# Knot_Thing_MCU.net
KiCad netlist of a schematic drawn in Altium Designer
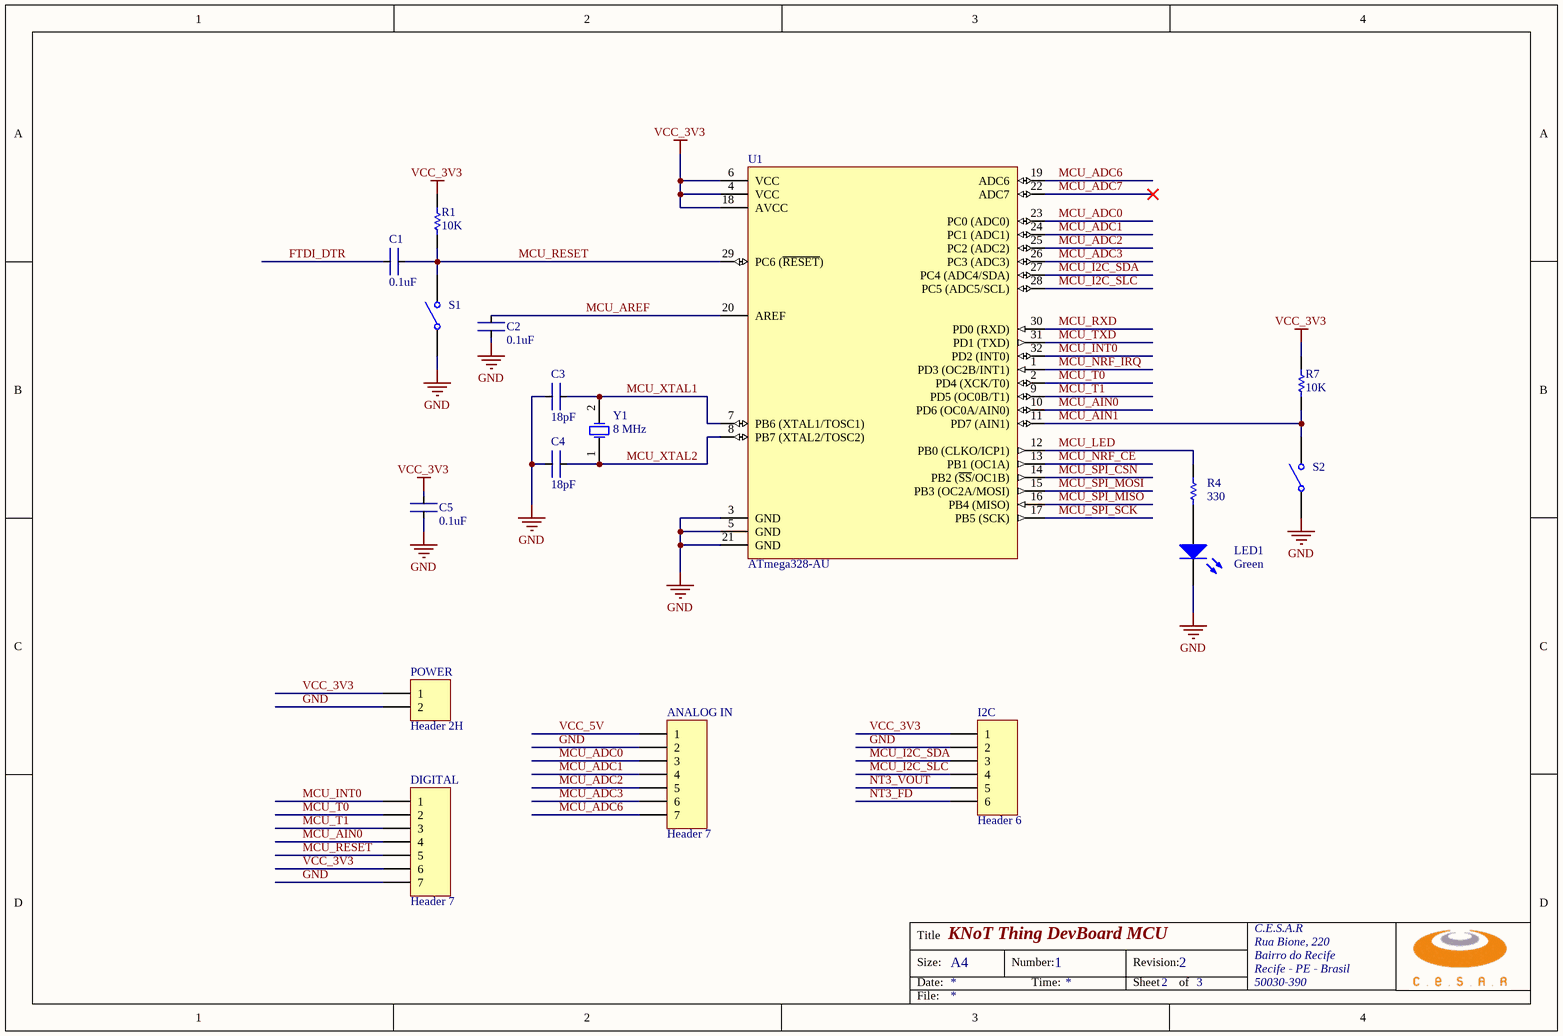
[diagram p0: Knot_Thing_MCU.SchDoc]

(export (version "E")
  (design (tool "Eeschema 10.0.6"))
  (components
    (comp (ref "ANALOG IN")
      (value "Header 7")
      (footprint "HDR1X7")
      (description "Header, 7-Pin")
      (fields (field (name "PUBLISHER") "Altium Limited"))
      (libsource (lib "KNoT_Thing") (part "Header 7"))
    )
    (comp (ref "C1")
      (value "0.1uF")
      (footprint "CAPC1005L")
      (description "Chip Capacitor 0402 (1005 metric)")
      (fields (field (name "Comment") "Cap_0402"))
      (libsource (lib "KNoT_Thing") (part "Capacitor_0402"))
    )
    (comp (ref "C2")
      (value "0.1uF")
      (footprint "CAPC1005L")
      (description "Chip Capacitor 0402 (1005 metric)")
      (fields (field (name "Comment") "Cap_0402"))
      (libsource (lib "KNoT_Thing") (part "Capacitor_0402"))
    )
    (comp (ref "C3")
      (value "18pF")
      (footprint "CAPC1005L")
      (description "Chip Capacitor 0402 (1005 metric)")
      (fields (field (name "Comment") "Cap_0402"))
      (libsource (lib "KNoT_Thing") (part "Capacitor_0402"))
    )
    (comp (ref "C4")
      (value "18pF")
      (footprint "CAPC1005L")
      (description "Chip Capacitor 0402 (1005 metric)")
      (fields (field (name "Comment") "Cap_0402"))
      (libsource (lib "KNoT_Thing") (part "Capacitor_0402"))
    )
    (comp (ref "C5")
      (value "0.1uF")
      (footprint "CAPC1005L")
      (description "Chip Capacitor 0402 (1005 metric)")
      (fields (field (name "Comment") "Cap_0402"))
      (libsource (lib "KNoT_Thing") (part "Capacitor_0402"))
    )
    (comp (ref "DIGITAL")
      (value "Header 7")
      (footprint "HDR1X7")
      (description "Header, 7-Pin")
      (fields (field (name "PUBLISHER") "Altium Limited"))
      (libsource (lib "KNoT_Thing") (part "Header 7"))
    )
    (comp (ref "I2C")
      (value "Header 6")
      (footprint "HDR1X6")
      (description "Header, 6-Pin")
      (fields (field (name "PUBLISHER") "Altium Limited"))
      (libsource (lib "KNoT_Thing") (part "Header 6"))
    )
    (comp (ref "LED1")
      (value "LED 0603")
      (footprint "0603_LED")
      (description "LED SMD 0603")
      (fields (field (name "COLOR") "Green"))
      (libsource (lib "KNoT_Thing") (part "LED 0603"))
    )
    (comp (ref "POWER")
      (value "Header 2H")
      (footprint "HDR1X2")
      (description "Header, 2-Pin, Right Angle")
      (fields (field (name "PUBLISHER") "Altium Limited"))
      (libsource (lib "KNoT_Thing") (part "Header 2H"))
    )
    (comp (ref "R1")
      (value "10K")
      (footprint "CAPC1005L")
      (fields (field (name "Comment") "RES_0402"))
      (libsource (lib "KNoT_Thing") (part "RES_0402"))
    )
    (comp (ref "R4")
      (value "330")
      (footprint "CAPC1005L")
      (fields (field (name "Comment") "RES_0402"))
      (libsource (lib "KNoT_Thing") (part "RES_0402"))
    )
    (comp (ref "R7")
      (value "10K")
      (footprint "CAPC1005L")
      (fields (field (name "Comment") "RES_0402"))
      (libsource (lib "KNoT_Thing") (part "RES_0402"))
    )
    (comp (ref "S1")
      (value "SW-SPST")
      (footprint "SWITCH TS-1181")
      (description "Single-Pole, Single-Throw Switch")
      (fields (field (name "PUBLISHER") "Altium Limited"))
      (libsource (lib "KNoT_Thing") (part "SW-SPST"))
    )
    (comp (ref "S2")
      (value "SW-SPST")
      (footprint "SWITCH TS-1181")
      (description "Single-Pole, Single-Throw Switch")
      (fields (field (name "PUBLISHER") "Altium Limited"))
      (libsource (lib "KNoT_Thing") (part "SW-SPST"))
    )
    (comp (ref "U1")
      (value "ATmega328-AU")
      (footprint "32A_L")
      (libsource (lib "KNoT_Thing") (part "ATmega328-AU"))
    )
    (comp (ref "Y1")
      (value "8 MHz")
      (footprint "CX5032GB")
      (description "Crystal FOXSLF/080-20")
      (libsource (lib "KNoT_Thing") (part "XTAL"))
    )
  )
  (nets
    (net (code "1") (name "/FTDI_DTR") (class "Default")
      (node (ref "C1") (pin "1") (pinfunction "1_1") (pintype "passive"))
    )
    (net (code "2") (name "/MCU_ADC0") (class "Default")
      (node (ref "ANALOG IN") (pin "3") (pinfunction "3_3") (pintype "passive"))
      (node (ref "U1") (pin "23") (pinfunction "PC0_(ADC0)_23") (pintype "bidirectional"))
    )
    (net (code "3") (name "/MCU_ADC1") (class "Default")
      (node (ref "ANALOG IN") (pin "4") (pinfunction "4_4") (pintype "passive"))
      (node (ref "U1") (pin "24") (pinfunction "PC1_(ADC1)_24") (pintype "bidirectional"))
    )
    (net (code "4") (name "/MCU_ADC2") (class "Default")
      (node (ref "ANALOG IN") (pin "5") (pinfunction "5_5") (pintype "passive"))
      (node (ref "U1") (pin "25") (pinfunction "PC2_(ADC2)_25") (pintype "bidirectional"))
    )
    (net (code "5") (name "/MCU_ADC3") (class "Default")
      (node (ref "ANALOG IN") (pin "6") (pinfunction "6_6") (pintype "passive"))
      (node (ref "U1") (pin "26") (pinfunction "PC3_(ADC3)_26") (pintype "bidirectional"))
    )
    (net (code "6") (name "/MCU_ADC6") (class "Default")
      (node (ref "ANALOG IN") (pin "7") (pinfunction "7_7") (pintype "passive"))
      (node (ref "U1") (pin "19") (pinfunction "ADC6_19") (pintype "bidirectional"))
    )
    (net (code "7") (name "/MCU_ADC7") (class "Default")
      (node (ref "U1") (pin "22") (pinfunction "ADC7_22") (pintype "bidirectional+no_connect"))
    )
    (net (code "8") (name "/MCU_AIN0") (class "Default")
      (node (ref "DIGITAL") (pin "4") (pinfunction "4_4") (pintype "passive"))
      (node (ref "U1") (pin "10") (pinfunction "PD6_(OC0A/AIN0)_10") (pintype "bidirectional"))
    )
    (net (code "9") (name "/MCU_AIN1") (class "Default")
      (node (ref "R7") (pin "1") (pinfunction "1_1") (pintype "passive"))
      (node (ref "S2") (pin "2") (pinfunction "NO_2") (pintype "passive"))
      (node (ref "U1") (pin "11") (pinfunction "PD7_(AIN1)_11") (pintype "bidirectional"))
    )
    (net (code "10") (name "/MCU_AREF") (class "Default")
      (node (ref "C2") (pin "2") (pinfunction "0_2") (pintype "passive"))
      (node (ref "U1") (pin "20") (pinfunction "AREF_20") (pintype "passive"))
    )
    (net (code "11") (name "/MCU_I2C_SDA") (class "Default")
      (node (ref "I2C") (pin "3") (pinfunction "3_3") (pintype "passive"))
      (node (ref "U1") (pin "27") (pinfunction "PC4_(ADC4/SDA)_27") (pintype "bidirectional"))
    )
    (net (code "12") (name "/MCU_I2C_SLC") (class "Default")
      (node (ref "I2C") (pin "4") (pinfunction "4_4") (pintype "passive"))
      (node (ref "U1") (pin "28") (pinfunction "PC5_(ADC5/SCL)_28") (pintype "bidirectional"))
    )
    (net (code "13") (name "/MCU_INT0") (class "Default")
      (node (ref "DIGITAL") (pin "1") (pinfunction "1_1") (pintype "passive"))
      (node (ref "U1") (pin "32") (pinfunction "PD2_(INT0)_32") (pintype "bidirectional"))
    )
    (net (code "14") (name "/MCU_LED") (class "Default")
      (node (ref "R4") (pin "2") (pinfunction "2_2") (pintype "passive"))
      (node (ref "U1") (pin "12") (pinfunction "PB0_(CLKO/ICP1)_12") (pintype "output"))
    )
    (net (code "15") (name "/MCU_NRF_CE") (class "Default")
      (node (ref "U1") (pin "13") (pinfunction "PB1_(OC1A)_13") (pintype "output"))
    )
    (net (code "16") (name "/MCU_NRF_IRQ") (class "Default")
      (node (ref "U1") (pin "1") (pinfunction "PD3_(OC2B/INT1)_1") (pintype "input"))
    )
    (net (code "17") (name "/MCU_RESET") (class "Default")
      (node (ref "C1") (pin "2") (pinfunction "0_2") (pintype "passive"))
      (node (ref "DIGITAL") (pin "5") (pinfunction "5_5") (pintype "passive"))
      (node (ref "R1") (pin "1") (pinfunction "1_1") (pintype "passive"))
      (node (ref "S1") (pin "2") (pinfunction "NO_2") (pintype "passive"))
      (node (ref "U1") (pin "29") (pinfunction "PC6_(~{RESET})_29") (pintype "bidirectional"))
    )
    (net (code "18") (name "/MCU_RXD") (class "Default")
      (node (ref "U1") (pin "30") (pinfunction "PD0_(RXD)_30") (pintype "input"))
    )
    (net (code "19") (name "/MCU_SPI_CSN") (class "Default")
      (node (ref "U1") (pin "14") (pinfunction "PB2_(~{SS}/OC1B)_14") (pintype "output"))
    )
    (net (code "20") (name "/MCU_SPI_MISO") (class "Default")
      (node (ref "U1") (pin "16") (pinfunction "PB4_(MISO)_16") (pintype "input"))
    )
    (net (code "21") (name "/MCU_SPI_MOSI") (class "Default")
      (node (ref "U1") (pin "15") (pinfunction "PB3_(OC2A/MOSI)_15") (pintype "output"))
    )
    (net (code "22") (name "/MCU_SPI_SCK") (class "Default")
      (node (ref "U1") (pin "17") (pinfunction "PB5_(SCK)_17") (pintype "output"))
    )
    (net (code "23") (name "/MCU_T0") (class "Default")
      (node (ref "DIGITAL") (pin "2") (pinfunction "2_2") (pintype "passive"))
      (node (ref "U1") (pin "2") (pinfunction "PD4_(XCK/T0)_2") (pintype "bidirectional"))
    )
    (net (code "24") (name "/MCU_T1") (class "Default")
      (node (ref "DIGITAL") (pin "3") (pinfunction "3_3") (pintype "passive"))
      (node (ref "U1") (pin "9") (pinfunction "PD5_(OC0B/T1)_9") (pintype "bidirectional"))
    )
    (net (code "25") (name "/MCU_TXD") (class "Default")
      (node (ref "U1") (pin "31") (pinfunction "PD1_(TXD)_31") (pintype "output"))
    )
    (net (code "26") (name "/MCU_XTAL1") (class "Default")
      (node (ref "C3") (pin "2") (pinfunction "0_2") (pintype "passive"))
      (node (ref "U1") (pin "7") (pinfunction "PB6_(XTAL1/TOSC1)_7") (pintype "bidirectional"))
      (node (ref "Y1") (pin "2") (pinfunction "OSC2_2") (pintype "passive"))
    )
    (net (code "27") (name "/MCU_XTAL2") (class "Default")
      (node (ref "C4") (pin "2") (pinfunction "0_2") (pintype "passive"))
      (node (ref "U1") (pin "8") (pinfunction "PB7_(XTAL2/TOSC2)_8") (pintype "bidirectional"))
      (node (ref "Y1") (pin "1") (pinfunction "OSC1_1") (pintype "passive"))
    )
    (net (code "28") (name "/NT3_FD") (class "Default")
      (node (ref "I2C") (pin "6") (pinfunction "6_6") (pintype "passive"))
    )
    (net (code "29") (name "/NT3_VOUT") (class "Default")
      (node (ref "I2C") (pin "5") (pinfunction "5_5") (pintype "passive"))
    )
    (net (code "30") (name "/VCC_5V") (class "Default")
      (node (ref "ANALOG IN") (pin "1") (pinfunction "1_1") (pintype "passive"))
    )
    (net (code "31") (name "GND") (class "Default")
      (node (ref "ANALOG IN") (pin "2") (pinfunction "2_2") (pintype "passive"))
      (node (ref "C2") (pin "1") (pinfunction "1_1") (pintype "passive"))
      (node (ref "C3") (pin "1") (pinfunction "1_1") (pintype "passive"))
      (node (ref "C4") (pin "1") (pinfunction "1_1") (pintype "passive"))
      (node (ref "C5") (pin "1") (pinfunction "1_1") (pintype "passive"))
      (node (ref "DIGITAL") (pin "7") (pinfunction "7_7") (pintype "passive"))
      (node (ref "I2C") (pin "2") (pinfunction "2_2") (pintype "passive"))
      (node (ref "LED1") (pin "2") (pinfunction "K_2") (pintype "passive"))
      (node (ref "POWER") (pin "2") (pinfunction "2_2") (pintype "passive"))
      (node (ref "S1") (pin "1") (pinfunction "COMMON_1") (pintype "passive"))
      (node (ref "S2") (pin "1") (pinfunction "COMMON_1") (pintype "passive"))
      (node (ref "U1") (pin "21") (pinfunction "GND_21") (pintype "power_in"))
      (node (ref "U1") (pin "3") (pinfunction "GND_3") (pintype "power_in"))
      (node (ref "U1") (pin "5") (pinfunction "GND_5") (pintype "power_in"))
    )
    (net (code "32") (name "Net-(LED1-A)") (class "Default")
      (node (ref "LED1") (pin "1") (pinfunction "A_1") (pintype "passive"))
      (node (ref "R4") (pin "1") (pinfunction "1_1") (pintype "passive"))
    )
    (net (code "33") (name "VCC_3V3") (class "Default")
      (node (ref "C5") (pin "2") (pinfunction "0_2") (pintype "passive"))
      (node (ref "DIGITAL") (pin "6") (pinfunction "6_6") (pintype "passive"))
      (node (ref "I2C") (pin "1") (pinfunction "1_1") (pintype "passive"))
      (node (ref "POWER") (pin "1") (pinfunction "1_1") (pintype "passive"))
      (node (ref "R1") (pin "2") (pinfunction "2_2") (pintype "passive"))
      (node (ref "R7") (pin "2") (pinfunction "2_2") (pintype "passive"))
      (node (ref "U1") (pin "18") (pinfunction "AVCC_18") (pintype "power_in"))
      (node (ref "U1") (pin "4") (pinfunction "VCC_4") (pintype "power_in"))
      (node (ref "U1") (pin "6") (pinfunction "VCC_6") (pintype "power_in"))
    )
  )
)
